# synapse_rpi3_adapter.net
KiCad netlist of a schematic drawn in EAGLE
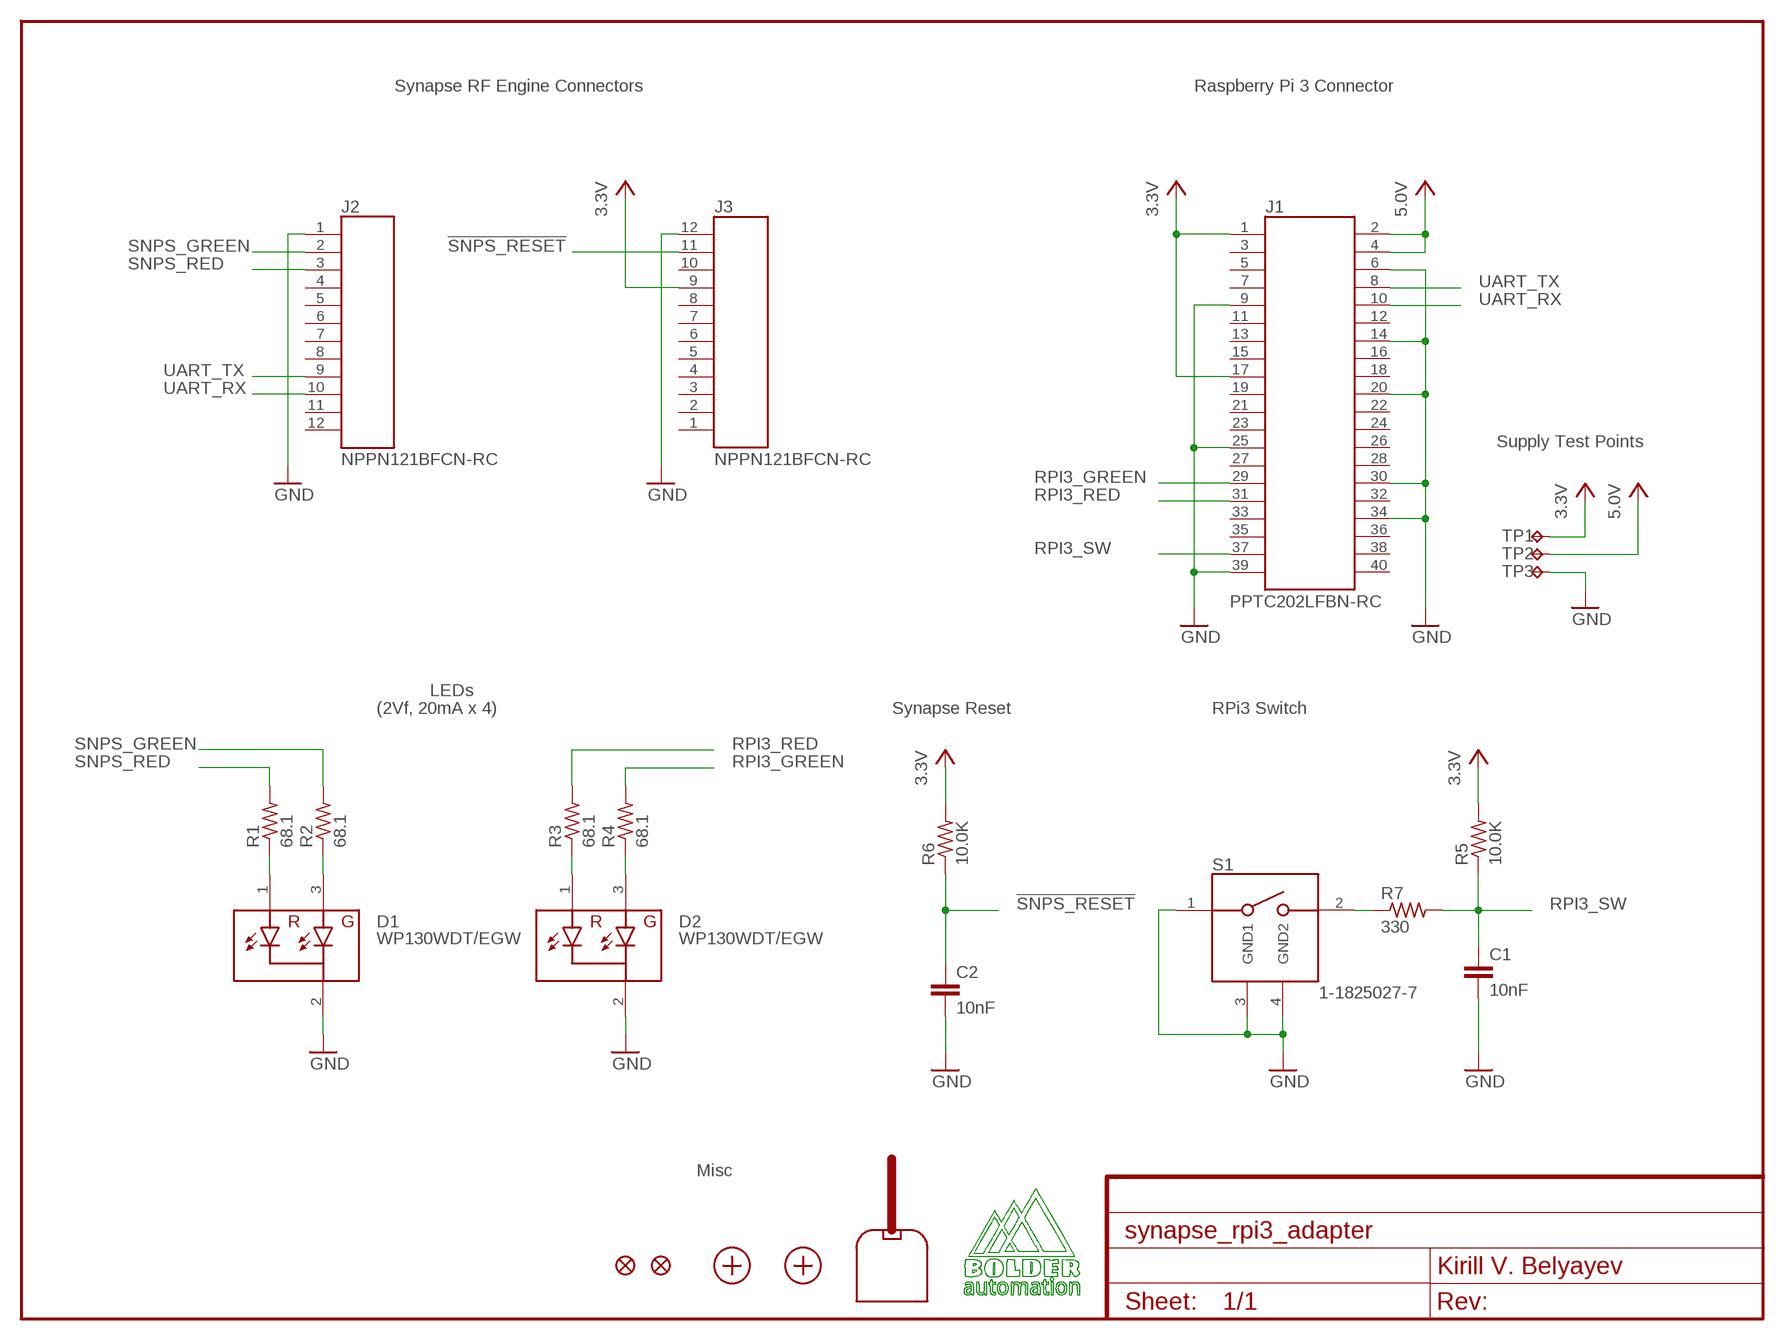
[diagram p0: schematic, sheet 1]

(export (version "E")
  (design (tool "Eeschema 10.0.6"))
  (components
    (comp (ref "C1")
      (value "10nF")
      (footprint "eagle-import:C0603")
      (libsource (lib "eagle-import") (part "C-EUC0603"))
    )
    (comp (ref "C2")
      (value "10nF")
      (footprint "eagle-import:C0603")
      (libsource (lib "eagle-import") (part "C-EUC0603"))
    )
    (comp (ref "D1")
      (value "WP130WDT/EGW")
      (footprint "eagle-import:WP130WDT_EGW")
      (fields (field (name "MANUFACTURER") "Kingbright"))
      (libsource (lib "eagle-import") (part "WP130WDT/EGW"))
    )
    (comp (ref "D2")
      (value "WP130WDT/EGW")
      (footprint "eagle-import:WP130WDT_EGW")
      (fields (field (name "MANUFACTURER") "Kingbright"))
      (libsource (lib "eagle-import") (part "WP130WDT/EGW"))
    )
    (comp (ref "FD1")
      (value "FIDUCIALUFIDUCIAL")
      (footprint "eagle-import:MICRO-FIDUCIAL")
      (libsource (lib "eagle-import") (part "FIDUCIALUFIDUCIAL"))
    )
    (comp (ref "FD2")
      (value "FIDUCIALUFIDUCIAL")
      (footprint "eagle-import:MICRO-FIDUCIAL")
      (libsource (lib "eagle-import") (part "FIDUCIALUFIDUCIAL"))
    )
    (comp (ref "J1")
      (value "PPTC202LFBN-RC")
      (footprint "eagle-import:PPTC202LFBN-RC")
      (fields (field (name "MANUFACTURER") "Sullins Connector Solutions"))
      (libsource (lib "eagle-import") (part "PPTC202LFBN-RC"))
    )
    (comp (ref "J2")
      (value "NPPN121BFCN-RC")
      (footprint "eagle-import:NPPN121BFCN-RC")
      (fields (field (name "MANUFACTURER") "Sullins Connector Solutions"))
      (libsource (lib "eagle-import") (part "NPPN121BFCN-RC"))
    )
    (comp (ref "J3")
      (value "NPPN121BFCN-RC")
      (footprint "eagle-import:NPPN121BFCN-RC")
      (fields (field (name "MANUFACTURER") "Sullins Connector Solutions"))
      (libsource (lib "eagle-import") (part "NPPN121BFCN-RC"))
    )
    (comp (ref "MNT1")
      (value "MOUNT-HOLE-NO-PLATE5.0MM")
      (footprint "eagle-import:MOUNT-HOLE-NO-PLATE-5.0MM")
      (libsource (lib "eagle-import") (part "MOUNT-HOLE-NO-PLATE5.0MM"))
    )
    (comp (ref "MNT2")
      (value "MOUNT-HOLE-NO-PLATE5.0MM")
      (footprint "eagle-import:MOUNT-HOLE-NO-PLATE-5.0MM")
      (libsource (lib "eagle-import") (part "MOUNT-HOLE-NO-PLATE5.0MM"))
    )
    (comp (ref "R1")
      (value "68.1")
      (footprint "eagle-import:R0603")
      (libsource (lib "eagle-import") (part "R-US_R0603"))
    )
    (comp (ref "R2")
      (value "68.1")
      (footprint "eagle-import:R0603")
      (libsource (lib "eagle-import") (part "R-US_R0603"))
    )
    (comp (ref "R3")
      (value "68.1")
      (footprint "eagle-import:R0603")
      (libsource (lib "eagle-import") (part "R-US_R0603"))
    )
    (comp (ref "R4")
      (value "68.1")
      (footprint "eagle-import:R0603")
      (libsource (lib "eagle-import") (part "R-US_R0603"))
    )
    (comp (ref "R5")
      (value "10.0K")
      (footprint "eagle-import:R0603")
      (libsource (lib "eagle-import") (part "R-US_R0603"))
    )
    (comp (ref "R6")
      (value "10.0K")
      (footprint "eagle-import:R0603")
      (libsource (lib "eagle-import") (part "R-US_R0603"))
    )
    (comp (ref "R7")
      (value "330")
      (footprint "eagle-import:R0603")
      (libsource (lib "eagle-import") (part "R-US_R0603"))
    )
    (comp (ref "S1")
      (value "1-1825027-7")
      (footprint "eagle-import:1-1825027-7")
      (fields (field (name "MANUFACTURER") "TE Connectivity"))
      (libsource (lib "eagle-import") (part "1-1825027-7"))
    )
    (comp (ref "TP1")
      (value "TEST-POINT")
      (footprint "eagle-import:TEST-POINT-40MILL")
      (libsource (lib "eagle-import") (part "TEST-POINT"))
    )
    (comp (ref "TP2")
      (value "TEST-POINT")
      (footprint "eagle-import:TEST-POINT-40MILL")
      (libsource (lib "eagle-import") (part "TEST-POINT"))
    )
    (comp (ref "TP3")
      (value "TEST-POINT")
      (footprint "eagle-import:TEST-POINT-40MILL")
      (libsource (lib "eagle-import") (part "TEST-POINT"))
    )
    (comp (ref "U$1")
      (value "BA_LOGO")
      (footprint "eagle-import:BA_LOGO")
      (libsource (lib "eagle-import") (part "BA_LOGO"))
    )
    (comp (ref "X1")
      (value "RF200PD1")
      (footprint "eagle-import:RF200PD1")
      (fields (field (name "MANUFACTURER") "Synapse Wireless"))
      (libsource (lib "eagle-import") (part "RF200PD1"))
    )
  )
  (nets
    (net (code "1") (name "/RPI3_GREEN") (class "Default")
      (node (ref "J1") (pin "29") (pinfunction "29_29") (pintype "bidirectional"))
      (node (ref "R4") (pin "2") (pinfunction "2_2") (pintype "passive"))
    )
    (net (code "2") (name "/RPI3_RED") (class "Default")
      (node (ref "J1") (pin "31") (pinfunction "31_31") (pintype "bidirectional"))
      (node (ref "R3") (pin "2") (pinfunction "2_2") (pintype "passive"))
    )
    (net (code "3") (name "/RPI3_SW") (class "Default")
      (node (ref "C1") (pin "1") (pinfunction "1_1") (pintype "passive"))
      (node (ref "J1") (pin "37") (pinfunction "37_37") (pintype "bidirectional"))
      (node (ref "R5") (pin "1") (pinfunction "1_1") (pintype "passive"))
      (node (ref "R7") (pin "2") (pinfunction "2_2") (pintype "passive"))
    )
    (net (code "4") (name "/SNPS_GREEN") (class "Default")
      (node (ref "J2") (pin "2") (pinfunction "P$2_2") (pintype "bidirectional"))
      (node (ref "R2") (pin "2") (pinfunction "2_2") (pintype "passive"))
    )
    (net (code "5") (name "/SNPS_RED") (class "Default")
      (node (ref "J2") (pin "3") (pinfunction "P$3_3") (pintype "bidirectional"))
      (node (ref "R1") (pin "2") (pinfunction "2_2") (pintype "passive"))
    )
    (net (code "6") (name "/UART_RX") (class "Default")
      (node (ref "J1") (pin "10") (pinfunction "10_10") (pintype "bidirectional"))
      (node (ref "J2") (pin "10") (pinfunction "P$10_10") (pintype "bidirectional"))
    )
    (net (code "7") (name "/UART_TX") (class "Default")
      (node (ref "J1") (pin "8") (pinfunction "8_8") (pintype "bidirectional"))
      (node (ref "J2") (pin "9") (pinfunction "P$9_9") (pintype "bidirectional"))
    )
    (net (code "8") (name "/~{SNPS_RESET}") (class "Default")
      (node (ref "C2") (pin "1") (pinfunction "1_1") (pintype "passive"))
      (node (ref "J3") (pin "11") (pinfunction "P$11_11") (pintype "bidirectional"))
      (node (ref "R6") (pin "1") (pinfunction "1_1") (pintype "passive"))
    )
    (net (code "9") (name "3.3V") (class "Default")
      (node (ref "J1") (pin "1") (pinfunction "1_1") (pintype "bidirectional"))
      (node (ref "J1") (pin "17") (pinfunction "17_17") (pintype "bidirectional"))
      (node (ref "J3") (pin "9") (pinfunction "P$9_9") (pintype "bidirectional"))
      (node (ref "R5") (pin "2") (pinfunction "2_2") (pintype "passive"))
      (node (ref "R6") (pin "2") (pinfunction "2_2") (pintype "passive"))
      (node (ref "TP1") (pin "1") (pinfunction "PP_1") (pintype "input"))
    )
    (net (code "10") (name "5.0V") (class "Default")
      (node (ref "J1") (pin "2") (pinfunction "2_2") (pintype "bidirectional"))
      (node (ref "J1") (pin "4") (pinfunction "4_4") (pintype "bidirectional"))
      (node (ref "TP2") (pin "1") (pinfunction "PP_1") (pintype "input"))
    )
    (net (code "11") (name "GND") (class "Default")
      (node (ref "C1") (pin "2") (pinfunction "2_2") (pintype "passive"))
      (node (ref "C2") (pin "2") (pinfunction "2_2") (pintype "passive"))
      (node (ref "D1") (pin "2") (pinfunction "P$2_2") (pintype "bidirectional"))
      (node (ref "D2") (pin "2") (pinfunction "P$2_2") (pintype "bidirectional"))
      (node (ref "J1") (pin "14") (pinfunction "14_14") (pintype "bidirectional"))
      (node (ref "J1") (pin "20") (pinfunction "20_20") (pintype "bidirectional"))
      (node (ref "J1") (pin "25") (pinfunction "25_25") (pintype "bidirectional"))
      (node (ref "J1") (pin "30") (pinfunction "30_30") (pintype "bidirectional"))
      (node (ref "J1") (pin "34") (pinfunction "34_34") (pintype "bidirectional"))
      (node (ref "J1") (pin "39") (pinfunction "39_39") (pintype "bidirectional"))
      (node (ref "J1") (pin "6") (pinfunction "6_6") (pintype "bidirectional"))
      (node (ref "J1") (pin "9") (pinfunction "9_9") (pintype "bidirectional"))
      (node (ref "J2") (pin "1") (pinfunction "P$1_1") (pintype "bidirectional"))
      (node (ref "J3") (pin "12") (pinfunction "P$12_12") (pintype "bidirectional"))
      (node (ref "S1") (pin "1") (pinfunction "P$1_1") (pintype "bidirectional"))
      (node (ref "S1") (pin "3") (pinfunction "GND1_3") (pintype "bidirectional"))
      (node (ref "S1") (pin "4") (pinfunction "GND2_4") (pintype "bidirectional"))
      (node (ref "TP3") (pin "1") (pinfunction "PP_1") (pintype "input"))
    )
    (net (code "12") (name "Net-(D1-GRN)") (class "Default")
      (node (ref "D1") (pin "3") (pinfunction "GRN_3") (pintype "bidirectional"))
      (node (ref "R2") (pin "1") (pinfunction "1_1") (pintype "passive"))
    )
    (net (code "13") (name "Net-(D1-RED)") (class "Default")
      (node (ref "D1") (pin "1") (pinfunction "RED_1") (pintype "bidirectional"))
      (node (ref "R1") (pin "1") (pinfunction "1_1") (pintype "passive"))
    )
    (net (code "14") (name "Net-(D2-GRN)") (class "Default")
      (node (ref "D2") (pin "3") (pinfunction "GRN_3") (pintype "bidirectional"))
      (node (ref "R4") (pin "1") (pinfunction "1_1") (pintype "passive"))
    )
    (net (code "15") (name "Net-(D2-RED)") (class "Default")
      (node (ref "D2") (pin "1") (pinfunction "RED_1") (pintype "bidirectional"))
      (node (ref "R3") (pin "1") (pinfunction "1_1") (pintype "passive"))
    )
    (net (code "16") (name "Net-(S1-P$2)") (class "Default")
      (node (ref "R7") (pin "1") (pinfunction "1_1") (pintype "passive"))
      (node (ref "S1") (pin "2") (pinfunction "P$2_2") (pintype "bidirectional"))
    )
    (net (code "17") (name "unconnected-(J1-Pad3)") (class "Default")
      (node (ref "J1") (pin "3") (pinfunction "3_3") (pintype "bidirectional"))
    )
    (net (code "18") (name "unconnected-(J1-Pad5)") (class "Default")
      (node (ref "J1") (pin "5") (pinfunction "5_5") (pintype "bidirectional"))
    )
    (net (code "19") (name "unconnected-(J1-Pad7)") (class "Default")
      (node (ref "J1") (pin "7") (pinfunction "7_7") (pintype "bidirectional"))
    )
    (net (code "20") (name "unconnected-(J1-Pad11)") (class "Default")
      (node (ref "J1") (pin "11") (pinfunction "11_11") (pintype "bidirectional"))
    )
    (net (code "21") (name "unconnected-(J1-Pad12)") (class "Default")
      (node (ref "J1") (pin "12") (pinfunction "12_12") (pintype "bidirectional"))
    )
    (net (code "22") (name "unconnected-(J1-Pad13)") (class "Default")
      (node (ref "J1") (pin "13") (pinfunction "13_13") (pintype "bidirectional"))
    )
    (net (code "23") (name "unconnected-(J1-Pad15)") (class "Default")
      (node (ref "J1") (pin "15") (pinfunction "15_15") (pintype "bidirectional"))
    )
    (net (code "24") (name "unconnected-(J1-Pad16)") (class "Default")
      (node (ref "J1") (pin "16") (pinfunction "16_16") (pintype "bidirectional"))
    )
    (net (code "25") (name "unconnected-(J1-Pad18)") (class "Default")
      (node (ref "J1") (pin "18") (pinfunction "18_18") (pintype "bidirectional"))
    )
    (net (code "26") (name "unconnected-(J1-Pad19)") (class "Default")
      (node (ref "J1") (pin "19") (pinfunction "19_19") (pintype "bidirectional"))
    )
    (net (code "27") (name "unconnected-(J1-Pad21)") (class "Default")
      (node (ref "J1") (pin "21") (pinfunction "21_21") (pintype "bidirectional"))
    )
    (net (code "28") (name "unconnected-(J1-Pad22)") (class "Default")
      (node (ref "J1") (pin "22") (pinfunction "22_22") (pintype "bidirectional"))
    )
    (net (code "29") (name "unconnected-(J1-Pad23)") (class "Default")
      (node (ref "J1") (pin "23") (pinfunction "23_23") (pintype "bidirectional"))
    )
    (net (code "30") (name "unconnected-(J1-Pad24)") (class "Default")
      (node (ref "J1") (pin "24") (pinfunction "24_24") (pintype "bidirectional"))
    )
    (net (code "31") (name "unconnected-(J1-Pad26)") (class "Default")
      (node (ref "J1") (pin "26") (pinfunction "26_26") (pintype "bidirectional"))
    )
    (net (code "32") (name "unconnected-(J1-Pad27)") (class "Default")
      (node (ref "J1") (pin "27") (pinfunction "27_27") (pintype "bidirectional"))
    )
    (net (code "33") (name "unconnected-(J1-Pad28)") (class "Default")
      (node (ref "J1") (pin "28") (pinfunction "28_28") (pintype "bidirectional"))
    )
    (net (code "34") (name "unconnected-(J1-Pad32)") (class "Default")
      (node (ref "J1") (pin "32") (pinfunction "32_32") (pintype "bidirectional"))
    )
    (net (code "35") (name "unconnected-(J1-Pad33)") (class "Default")
      (node (ref "J1") (pin "33") (pinfunction "33_33") (pintype "bidirectional"))
    )
    (net (code "36") (name "unconnected-(J1-Pad35)") (class "Default")
      (node (ref "J1") (pin "35") (pinfunction "35_35") (pintype "bidirectional"))
    )
    (net (code "37") (name "unconnected-(J1-Pad36)") (class "Default")
      (node (ref "J1") (pin "36") (pinfunction "36_36") (pintype "bidirectional"))
    )
    (net (code "38") (name "unconnected-(J1-Pad38)") (class "Default")
      (node (ref "J1") (pin "38") (pinfunction "38_38") (pintype "bidirectional"))
    )
    (net (code "39") (name "unconnected-(J1-Pad40)") (class "Default")
      (node (ref "J1") (pin "40") (pinfunction "40_40") (pintype "bidirectional"))
    )
    (net (code "40") (name "unconnected-(J2-P$4-Pad4)") (class "Default")
      (node (ref "J2") (pin "4") (pinfunction "P$4_4") (pintype "bidirectional"))
    )
    (net (code "41") (name "unconnected-(J2-P$5-Pad5)") (class "Default")
      (node (ref "J2") (pin "5") (pinfunction "P$5_5") (pintype "bidirectional"))
    )
    (net (code "42") (name "unconnected-(J2-P$6-Pad6)") (class "Default")
      (node (ref "J2") (pin "6") (pinfunction "P$6_6") (pintype "bidirectional"))
    )
    (net (code "43") (name "unconnected-(J2-P$7-Pad7)") (class "Default")
      (node (ref "J2") (pin "7") (pinfunction "P$7_7") (pintype "bidirectional"))
    )
    (net (code "44") (name "unconnected-(J2-P$8-Pad8)") (class "Default")
      (node (ref "J2") (pin "8") (pinfunction "P$8_8") (pintype "bidirectional"))
    )
    (net (code "45") (name "unconnected-(J2-P$11-Pad11)") (class "Default")
      (node (ref "J2") (pin "11") (pinfunction "P$11_11") (pintype "bidirectional"))
    )
    (net (code "46") (name "unconnected-(J2-P$12-Pad12)") (class "Default")
      (node (ref "J2") (pin "12") (pinfunction "P$12_12") (pintype "bidirectional"))
    )
    (net (code "47") (name "unconnected-(J3-P$1-Pad1)") (class "Default")
      (node (ref "J3") (pin "1") (pinfunction "P$1_1") (pintype "bidirectional"))
    )
    (net (code "48") (name "unconnected-(J3-P$2-Pad2)") (class "Default")
      (node (ref "J3") (pin "2") (pinfunction "P$2_2") (pintype "bidirectional"))
    )
    (net (code "49") (name "unconnected-(J3-P$3-Pad3)") (class "Default")
      (node (ref "J3") (pin "3") (pinfunction "P$3_3") (pintype "bidirectional"))
    )
    (net (code "50") (name "unconnected-(J3-P$4-Pad4)") (class "Default")
      (node (ref "J3") (pin "4") (pinfunction "P$4_4") (pintype "bidirectional"))
    )
    (net (code "51") (name "unconnected-(J3-P$5-Pad5)") (class "Default")
      (node (ref "J3") (pin "5") (pinfunction "P$5_5") (pintype "bidirectional"))
    )
    (net (code "52") (name "unconnected-(J3-P$6-Pad6)") (class "Default")
      (node (ref "J3") (pin "6") (pinfunction "P$6_6") (pintype "bidirectional"))
    )
    (net (code "53") (name "unconnected-(J3-P$7-Pad7)") (class "Default")
      (node (ref "J3") (pin "7") (pinfunction "P$7_7") (pintype "bidirectional"))
    )
    (net (code "54") (name "unconnected-(J3-P$8-Pad8)") (class "Default")
      (node (ref "J3") (pin "8") (pinfunction "P$8_8") (pintype "bidirectional"))
    )
    (net (code "55") (name "unconnected-(J3-P$10-Pad10)") (class "Default")
      (node (ref "J3") (pin "10") (pinfunction "P$10_10") (pintype "bidirectional"))
    )
  )
)
